# MyProSch1.net
KiCad netlist of a schematic drawn in Altium Designer
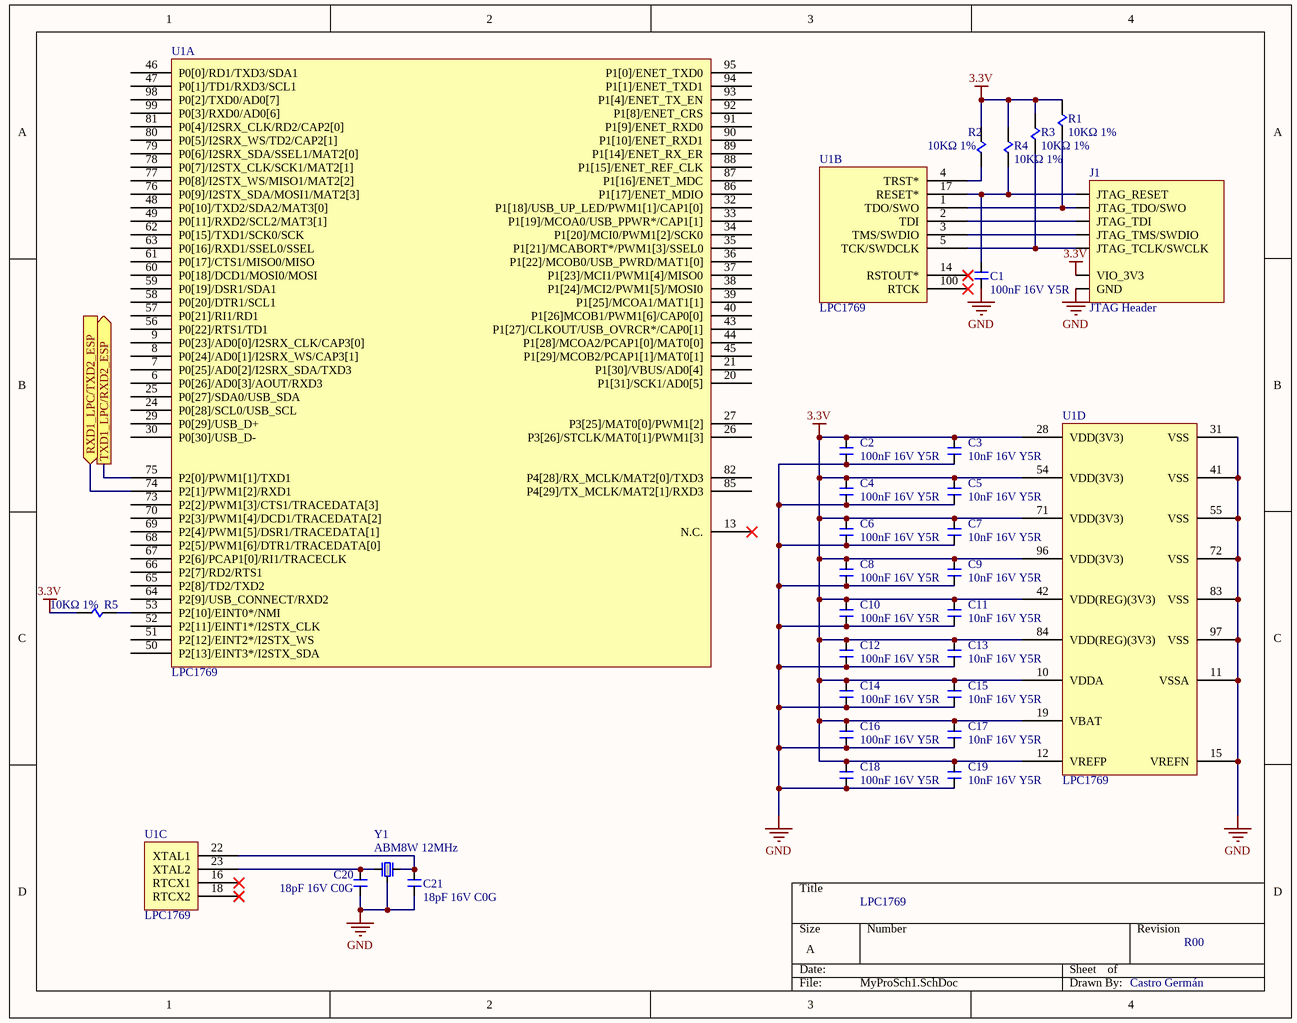
[diagram p0: MyProSch1.SchDoc]

(export (version "E")
  (design (tool "Eeschema 10.0.6"))
  (components
    (comp (ref "C1")
      (value "100nF 16V Y5R")
      (footprint "C_0805")
      (description "Capacitor")
      (libsource (lib "MyPro") (part "Capacitor"))
    )
    (comp (ref "C2")
      (value "100nF 16V Y5R")
      (footprint "C_0805")
      (description "Capacitor")
      (libsource (lib "MyPro") (part "Capacitor"))
    )
    (comp (ref "C3")
      (value "10nF 16V Y5R")
      (footprint "C_0805")
      (description "Capacitor")
      (libsource (lib "MyPro") (part "Capacitor"))
    )
    (comp (ref "C4")
      (value "100nF 16V Y5R")
      (footprint "C_0805")
      (description "Capacitor")
      (libsource (lib "MyPro") (part "Capacitor"))
    )
    (comp (ref "C5")
      (value "10nF 16V Y5R")
      (footprint "C_0805")
      (description "Capacitor")
      (libsource (lib "MyPro") (part "Capacitor"))
    )
    (comp (ref "C6")
      (value "100nF 16V Y5R")
      (footprint "C_0805")
      (description "Capacitor")
      (libsource (lib "MyPro") (part "Capacitor"))
    )
    (comp (ref "C7")
      (value "10nF 16V Y5R")
      (footprint "C_0805")
      (description "Capacitor")
      (libsource (lib "MyPro") (part "Capacitor"))
    )
    (comp (ref "C8")
      (value "100nF 16V Y5R")
      (footprint "C_0805")
      (description "Capacitor")
      (libsource (lib "MyPro") (part "Capacitor"))
    )
    (comp (ref "C9")
      (value "10nF 16V Y5R")
      (footprint "C_0805")
      (description "Capacitor")
      (libsource (lib "MyPro") (part "Capacitor"))
    )
    (comp (ref "C10")
      (value "100nF 16V Y5R")
      (footprint "C_0805")
      (description "Capacitor")
      (libsource (lib "MyPro") (part "Capacitor"))
    )
    (comp (ref "C11")
      (value "10nF 16V Y5R")
      (footprint "C_0805")
      (description "Capacitor")
      (libsource (lib "MyPro") (part "Capacitor"))
    )
    (comp (ref "C12")
      (value "100nF 16V Y5R")
      (footprint "C_0805")
      (description "Capacitor")
      (libsource (lib "MyPro") (part "Capacitor"))
    )
    (comp (ref "C13")
      (value "10nF 16V Y5R")
      (footprint "C_0805")
      (description "Capacitor")
      (libsource (lib "MyPro") (part "Capacitor"))
    )
    (comp (ref "C14")
      (value "100nF 16V Y5R")
      (footprint "C_0805")
      (description "Capacitor")
      (libsource (lib "MyPro") (part "Capacitor"))
    )
    (comp (ref "C15")
      (value "10nF 16V Y5R")
      (footprint "C_0805")
      (description "Capacitor")
      (libsource (lib "MyPro") (part "Capacitor"))
    )
    (comp (ref "C16")
      (value "100nF 16V Y5R")
      (footprint "C_0805")
      (description "Capacitor")
      (libsource (lib "MyPro") (part "Capacitor"))
    )
    (comp (ref "C17")
      (value "10nF 16V Y5R")
      (footprint "C_0805")
      (description "Capacitor")
      (libsource (lib "MyPro") (part "Capacitor"))
    )
    (comp (ref "C18")
      (value "100nF 16V Y5R")
      (footprint "C_0805")
      (description "Capacitor")
      (libsource (lib "MyPro") (part "Capacitor"))
    )
    (comp (ref "C19")
      (value "10nF 16V Y5R")
      (footprint "C_0805")
      (description "Capacitor")
      (libsource (lib "MyPro") (part "Capacitor"))
    )
    (comp (ref "C20")
      (value "18pF 16V C0G")
      (footprint "C_0805")
      (description "Capacitor")
      (libsource (lib "MyPro") (part "Capacitor"))
    )
    (comp (ref "C21")
      (value "18pF 16V C0G")
      (footprint "C_0805")
      (description "Capacitor")
      (libsource (lib "MyPro") (part "Capacitor"))
    )
    (comp (ref "J1") (value "JTAG Header") (libsource (lib "MyPro") (part "JTAG Header")))
    (comp (ref "R1")
      (value "10KΩ 1%")
      (footprint "R_0805")
      (description "Resistor")
      (libsource (lib "MyPro") (part "Resistor"))
    )
    (comp (ref "R2")
      (value "10KΩ 1%")
      (footprint "R_0805")
      (description "Resistor")
      (libsource (lib "MyPro") (part "Resistor"))
    )
    (comp (ref "R3")
      (value "10KΩ 1%")
      (footprint "R_0805")
      (description "Resistor")
      (libsource (lib "MyPro") (part "Resistor"))
    )
    (comp (ref "R4")
      (value "10KΩ 1%")
      (footprint "R_0805")
      (description "Resistor")
      (libsource (lib "MyPro") (part "Resistor"))
    )
    (comp (ref "R5")
      (value "10KΩ 1%")
      (footprint "R_0805")
      (description "Resistor")
      (libsource (lib "MyPro") (part "Resistor"))
    )
    (comp (ref "U1")
      (value "LPC1769")
      (footprint "LQFP100")
      (description "32 bit ARM Cortex M3")
      (libsource (lib "MyPro") (part "LPC1769"))
    )
    (comp (ref "Y1")
      (value "ABM8W 12MHz")
      (footprint "ABM8W")
      (description "Crystal")
      (libsource (lib "MyPro") (part "Crystal"))
    )
  )
  (nets
    (net (code "1") (name "/RXD1_LPC{slash}TXD2_ESP") (class "Default")
      (node (ref "U1") (pin "74") (pinfunction "P2[1]/PWM1[2]/RXD1_74") (pintype "passive"))
    )
    (net (code "2") (name "/TXD1_LPC{slash}RXD2_ESP") (class "Default")
      (node (ref "U1") (pin "75") (pinfunction "P2[0]/PWM1[1]/TXD1_75") (pintype "passive"))
    )
    (net (code "3") (name "3.3V") (class "Default")
      (node (ref "C10") (pin "1") (pinfunction "A1_1") (pintype "passive"))
      (node (ref "C11") (pin "1") (pinfunction "A1_1") (pintype "passive"))
      (node (ref "C12") (pin "1") (pinfunction "A1_1") (pintype "passive"))
      (node (ref "C13") (pin "1") (pinfunction "A1_1") (pintype "passive"))
      (node (ref "C14") (pin "1") (pinfunction "A1_1") (pintype "passive"))
      (node (ref "C15") (pin "1") (pinfunction "A1_1") (pintype "passive"))
      (node (ref "C16") (pin "1") (pinfunction "A1_1") (pintype "passive"))
      (node (ref "C17") (pin "1") (pinfunction "A1_1") (pintype "passive"))
      (node (ref "C18") (pin "1") (pinfunction "A1_1") (pintype "passive"))
      (node (ref "C19") (pin "1") (pinfunction "A1_1") (pintype "passive"))
      (node (ref "C2") (pin "1") (pinfunction "A1_1") (pintype "passive"))
      (node (ref "C3") (pin "1") (pinfunction "A1_1") (pintype "passive"))
      (node (ref "C4") (pin "1") (pinfunction "A1_1") (pintype "passive"))
      (node (ref "C5") (pin "1") (pinfunction "A1_1") (pintype "passive"))
      (node (ref "C6") (pin "1") (pinfunction "A1_1") (pintype "passive"))
      (node (ref "C7") (pin "1") (pinfunction "A1_1") (pintype "passive"))
      (node (ref "C8") (pin "1") (pinfunction "A1_1") (pintype "passive"))
      (node (ref "C9") (pin "1") (pinfunction "A1_1") (pintype "passive"))
      (node (ref "J1") (pin "1") (pinfunction "VIO_3V3_1") (pintype "passive"))
      (node (ref "R1") (pin "2") (pinfunction "P2_2") (pintype "passive"))
      (node (ref "R2") (pin "2") (pinfunction "P2_2") (pintype "passive"))
      (node (ref "R3") (pin "2") (pinfunction "P2_2") (pintype "passive"))
      (node (ref "R4") (pin "2") (pinfunction "P2_2") (pintype "passive"))
      (node (ref "R5") (pin "1") (pinfunction "P1_1") (pintype "passive"))
      (node (ref "U1") (pin "10") (pinfunction "VDDA_10") (pintype "passive"))
      (node (ref "U1") (pin "12") (pinfunction "VREFP_12") (pintype "passive"))
      (node (ref "U1") (pin "19") (pinfunction "VBAT_19") (pintype "passive"))
      (node (ref "U1") (pin "28") (pinfunction "VDD(3V3)_28") (pintype "passive"))
      (node (ref "U1") (pin "42") (pinfunction "VDD(REG)(3V3)_42") (pintype "passive"))
      (node (ref "U1") (pin "54") (pinfunction "VDD(3V3)_54") (pintype "passive"))
      (node (ref "U1") (pin "71") (pinfunction "VDD(3V3)_71") (pintype "passive"))
      (node (ref "U1") (pin "84") (pinfunction "VDD(REG)(3V3)_84") (pintype "passive"))
      (node (ref "U1") (pin "96") (pinfunction "VDD(3V3)_96") (pintype "passive"))
    )
    (net (code "4") (name "GND") (class "Default")
      (node (ref "C1") (pin "2") (pinfunction "A2_2") (pintype "passive"))
      (node (ref "C10") (pin "2") (pinfunction "A2_2") (pintype "passive"))
      (node (ref "C11") (pin "2") (pinfunction "A2_2") (pintype "passive"))
      (node (ref "C12") (pin "2") (pinfunction "A2_2") (pintype "passive"))
      (node (ref "C13") (pin "2") (pinfunction "A2_2") (pintype "passive"))
      (node (ref "C14") (pin "2") (pinfunction "A2_2") (pintype "passive"))
      (node (ref "C15") (pin "2") (pinfunction "A2_2") (pintype "passive"))
      (node (ref "C16") (pin "2") (pinfunction "A2_2") (pintype "passive"))
      (node (ref "C17") (pin "2") (pinfunction "A2_2") (pintype "passive"))
      (node (ref "C18") (pin "2") (pinfunction "A2_2") (pintype "passive"))
      (node (ref "C19") (pin "2") (pinfunction "A2_2") (pintype "passive"))
      (node (ref "C2") (pin "2") (pinfunction "A2_2") (pintype "passive"))
      (node (ref "C20") (pin "2") (pinfunction "A2_2") (pintype "passive"))
      (node (ref "C21") (pin "2") (pinfunction "A2_2") (pintype "passive"))
      (node (ref "C3") (pin "2") (pinfunction "A2_2") (pintype "passive"))
      (node (ref "C4") (pin "2") (pinfunction "A2_2") (pintype "passive"))
      (node (ref "C5") (pin "2") (pinfunction "A2_2") (pintype "passive"))
      (node (ref "C6") (pin "2") (pinfunction "A2_2") (pintype "passive"))
      (node (ref "C7") (pin "2") (pinfunction "A2_2") (pintype "passive"))
      (node (ref "C8") (pin "2") (pinfunction "A2_2") (pintype "passive"))
      (node (ref "C9") (pin "2") (pinfunction "A2_2") (pintype "passive"))
      (node (ref "J1") (pin "8") (pinfunction "GND_8") (pintype "passive"))
      (node (ref "U1") (pin "11") (pinfunction "VSSA_11") (pintype "passive"))
      (node (ref "U1") (pin "15") (pinfunction "VREFN_15") (pintype "passive"))
      (node (ref "U1") (pin "31") (pinfunction "VSS_31") (pintype "passive"))
      (node (ref "U1") (pin "41") (pinfunction "VSS_41") (pintype "passive"))
      (node (ref "U1") (pin "55") (pinfunction "VSS_55") (pintype "passive"))
      (node (ref "U1") (pin "72") (pinfunction "VSS_72") (pintype "passive"))
      (node (ref "U1") (pin "83") (pinfunction "VSS_83") (pintype "passive"))
      (node (ref "U1") (pin "97") (pinfunction "VSS_97") (pintype "passive"))
      (node (ref "Y1") (pin "3") (pinfunction "P3_3") (pintype "passive"))
    )
    (net (code "5") (name "Net-(C1-A1)") (class "Default")
      (node (ref "C1") (pin "1") (pinfunction "A1_1") (pintype "passive"))
      (node (ref "J1") (pin "6") (pinfunction "JTAG_RESET_6") (pintype "passive"))
      (node (ref "R4") (pin "1") (pinfunction "P1_1") (pintype "passive"))
      (node (ref "U1") (pin "17") (pinfunction "RESET*_17") (pintype "passive"))
    )
    (net (code "6") (name "Net-(C20-A1)") (class "Default")
      (node (ref "C20") (pin "1") (pinfunction "A1_1") (pintype "passive"))
      (node (ref "U1") (pin "23") (pinfunction "XTAL2_23") (pintype "passive"))
      (node (ref "Y1") (pin "1") (pinfunction "P1_1") (pintype "passive"))
    )
    (net (code "7") (name "Net-(C21-A1)") (class "Default")
      (node (ref "C21") (pin "1") (pinfunction "A1_1") (pintype "passive"))
      (node (ref "U1") (pin "22") (pinfunction "XTAL1_22") (pintype "passive"))
      (node (ref "Y1") (pin "2") (pinfunction "P2_2") (pintype "passive"))
    )
    (net (code "8") (name "Net-(J1-JTAG_TCLK{slash}SWCLK)") (class "Default")
      (node (ref "J1") (pin "3") (pinfunction "JTAG_TCLK/SWCLK_3") (pintype "passive"))
      (node (ref "R3") (pin "1") (pinfunction "P1_1") (pintype "passive"))
      (node (ref "U1") (pin "5") (pinfunction "TCK/SWDCLK_5") (pintype "passive"))
    )
    (net (code "9") (name "Net-(J1-JTAG_TDI)") (class "Default")
      (node (ref "J1") (pin "5") (pinfunction "JTAG_TDI_5") (pintype "passive"))
      (node (ref "U1") (pin "2") (pinfunction "TDI_2") (pintype "passive"))
    )
    (net (code "10") (name "Net-(J1-JTAG_TDO{slash}SWO)") (class "Default")
      (node (ref "J1") (pin "4") (pinfunction "JTAG_TDO/SWO_4") (pintype "passive"))
      (node (ref "R1") (pin "1") (pinfunction "P1_1") (pintype "passive"))
      (node (ref "U1") (pin "1") (pinfunction "TDO/SWO_1") (pintype "passive"))
    )
    (net (code "11") (name "Net-(J1-JTAG_TMS{slash}SWDIO)") (class "Default")
      (node (ref "J1") (pin "2") (pinfunction "JTAG_TMS/SWDIO_2") (pintype "passive"))
      (node (ref "U1") (pin "3") (pinfunction "TMS/SWDIO_3") (pintype "passive"))
    )
    (net (code "12") (name "Net-(R2-P1)") (class "Default")
      (node (ref "R2") (pin "1") (pinfunction "P1_1") (pintype "passive"))
      (node (ref "U1") (pin "4") (pinfunction "TRST*_4") (pintype "passive"))
    )
    (net (code "13") (name "Net-(R5-P2)") (class "Default")
      (node (ref "R5") (pin "2") (pinfunction "P2_2") (pintype "passive"))
      (node (ref "U1") (pin "53") (pinfunction "P2[10]/EINT0*/NMI_53") (pintype "passive"))
    )
    (net (code "14") (name "unconnected-(U1A-N.C.-Pad13)") (class "Default")
      (node (ref "U1") (pin "13") (pinfunction "N.C._13") (pintype "passive+no_connect"))
    )
    (net (code "15") (name "unconnected-(U1A-P0[0]{slash}RD1{slash}TXD3{slash}SDA1-Pad46)") (class "Default")
      (node (ref "U1") (pin "46") (pinfunction "P0[0]/RD1/TXD3/SDA1_46") (pintype "passive"))
    )
    (net (code "16") (name "unconnected-(U1A-P0[1]{slash}TD1{slash}RXD3{slash}SCL1-Pad47)") (class "Default")
      (node (ref "U1") (pin "47") (pinfunction "P0[1]/TD1/RXD3/SCL1_47") (pintype "passive"))
    )
    (net (code "17") (name "unconnected-(U1A-P0[2]{slash}TXD0{slash}AD0[7]-Pad98)") (class "Default")
      (node (ref "U1") (pin "98") (pinfunction "P0[2]/TXD0/AD0[7]_98") (pintype "passive"))
    )
    (net (code "18") (name "unconnected-(U1A-P0[3]{slash}RXD0{slash}AD0[6]-Pad99)") (class "Default")
      (node (ref "U1") (pin "99") (pinfunction "P0[3]/RXD0/AD0[6]_99") (pintype "passive"))
    )
    (net (code "19") (name "unconnected-(U1A-P0[4]{slash}I2SRX_CLK{slash}RD2{slash}CAP2[0]-Pad81)") (class "Default")
      (node (ref "U1") (pin "81") (pinfunction "P0[4]/I2SRX_CLK/RD2/CAP2[0]_81") (pintype "passive"))
    )
    (net (code "20") (name "unconnected-(U1A-P0[5]{slash}I2SRX_WS{slash}TD2{slash}CAP2[1]-Pad80)") (class "Default")
      (node (ref "U1") (pin "80") (pinfunction "P0[5]/I2SRX_WS/TD2/CAP2[1]_80") (pintype "passive"))
    )
    (net (code "21") (name "unconnected-(U1A-P0[6]{slash}I2SRX_SDA{slash}SSEL1{slash}MAT2[0]-Pad79)") (class "Default")
      (node (ref "U1") (pin "79") (pinfunction "P0[6]/I2SRX_SDA/SSEL1/MAT2[0]_79") (pintype "passive"))
    )
    (net (code "22") (name "unconnected-(U1A-P0[7]{slash}I2STX_CLK{slash}SCK1{slash}MAT2[1]-Pad78)") (class "Default")
      (node (ref "U1") (pin "78") (pinfunction "P0[7]/I2STX_CLK/SCK1/MAT2[1]_78") (pintype "passive"))
    )
    (net (code "23") (name "unconnected-(U1A-P0[8]{slash}I2STX_WS{slash}MISO1{slash}MAT2[2]-Pad77)") (class "Default")
      (node (ref "U1") (pin "77") (pinfunction "P0[8]/I2STX_WS/MISO1/MAT2[2]_77") (pintype "passive"))
    )
    (net (code "24") (name "unconnected-(U1A-P0[9]{slash}I2STX_SDA{slash}MOSI1{slash}MAT2[3]-Pad76)") (class "Default")
      (node (ref "U1") (pin "76") (pinfunction "P0[9]/I2STX_SDA/MOSI1/MAT2[3]_76") (pintype "passive"))
    )
    (net (code "25") (name "unconnected-(U1A-P0[10]{slash}TXD2{slash}SDA2{slash}MAT3[0]-Pad48)") (class "Default")
      (node (ref "U1") (pin "48") (pinfunction "P0[10]/TXD2/SDA2/MAT3[0]_48") (pintype "passive"))
    )
    (net (code "26") (name "unconnected-(U1A-P0[11]{slash}RXD2{slash}SCL2{slash}MAT3[1]-Pad49)") (class "Default")
      (node (ref "U1") (pin "49") (pinfunction "P0[11]/RXD2/SCL2/MAT3[1]_49") (pintype "passive"))
    )
    (net (code "27") (name "unconnected-(U1A-P0[15]{slash}TXD1{slash}SCK0{slash}SCK-Pad62)") (class "Default")
      (node (ref "U1") (pin "62") (pinfunction "P0[15]/TXD1/SCK0/SCK_62") (pintype "passive"))
    )
    (net (code "28") (name "unconnected-(U1A-P0[16]{slash}RXD1{slash}SSEL0{slash}SSEL-Pad63)") (class "Default")
      (node (ref "U1") (pin "63") (pinfunction "P0[16]/RXD1/SSEL0/SSEL_63") (pintype "passive"))
    )
    (net (code "29") (name "unconnected-(U1A-P0[17]{slash}CTS1{slash}MISO0{slash}MISO-Pad61)") (class "Default")
      (node (ref "U1") (pin "61") (pinfunction "P0[17]/CTS1/MISO0/MISO_61") (pintype "passive"))
    )
    (net (code "30") (name "unconnected-(U1A-P0[18]{slash}DCD1{slash}MOSI0{slash}MOSI-Pad60)") (class "Default")
      (node (ref "U1") (pin "60") (pinfunction "P0[18]/DCD1/MOSI0/MOSI_60") (pintype "passive"))
    )
    (net (code "31") (name "unconnected-(U1A-P0[19]{slash}DSR1{slash}SDA1-Pad59)") (class "Default")
      (node (ref "U1") (pin "59") (pinfunction "P0[19]/DSR1/SDA1_59") (pintype "passive"))
    )
    (net (code "32") (name "unconnected-(U1A-P0[20]{slash}DTR1{slash}SCL1-Pad58)") (class "Default")
      (node (ref "U1") (pin "58") (pinfunction "P0[20]/DTR1/SCL1_58") (pintype "passive"))
    )
    (net (code "33") (name "unconnected-(U1A-P0[21]{slash}RI1{slash}RD1-Pad57)") (class "Default")
      (node (ref "U1") (pin "57") (pinfunction "P0[21]/RI1/RD1_57") (pintype "passive"))
    )
    (net (code "34") (name "unconnected-(U1A-P0[22]{slash}RTS1{slash}TD1-Pad56)") (class "Default")
      (node (ref "U1") (pin "56") (pinfunction "P0[22]/RTS1/TD1_56") (pintype "passive"))
    )
    (net (code "35") (name "unconnected-(U1A-P0[23]{slash}AD0[0]{slash}I2SRX_CLK{slash}CAP3[0]-Pad9)") (class "Default")
      (node (ref "U1") (pin "9") (pinfunction "P0[23]/AD0[0]/I2SRX_CLK/CAP3[0]_9") (pintype "passive"))
    )
    (net (code "36") (name "unconnected-(U1A-P0[24]{slash}AD0[1]{slash}I2SRX_WS{slash}CAP3[1]-Pad8)") (class "Default")
      (node (ref "U1") (pin "8") (pinfunction "P0[24]/AD0[1]/I2SRX_WS/CAP3[1]_8") (pintype "passive"))
    )
    (net (code "37") (name "unconnected-(U1A-P0[25]{slash}AD0[2]{slash}I2SRX_SDA{slash}TXD3-Pad7)") (class "Default")
      (node (ref "U1") (pin "7") (pinfunction "P0[25]/AD0[2]/I2SRX_SDA/TXD3_7") (pintype "passive"))
    )
    (net (code "38") (name "unconnected-(U1A-P0[26]{slash}AD0[3]{slash}AOUT{slash}RXD3-Pad6)") (class "Default")
      (node (ref "U1") (pin "6") (pinfunction "P0[26]/AD0[3]/AOUT/RXD3_6") (pintype "passive"))
    )
    (net (code "39") (name "unconnected-(U1A-P0[27]{slash}SDA0{slash}USB_SDA-Pad25)") (class "Default")
      (node (ref "U1") (pin "25") (pinfunction "P0[27]/SDA0/USB_SDA_25") (pintype "passive"))
    )
    (net (code "40") (name "unconnected-(U1A-P0[28]{slash}SCL0{slash}USB_SCL-Pad24)") (class "Default")
      (node (ref "U1") (pin "24") (pinfunction "P0[28]/SCL0/USB_SCL_24") (pintype "passive"))
    )
    (net (code "41") (name "unconnected-(U1A-P0[29]{slash}USB_D+-Pad29)") (class "Default")
      (node (ref "U1") (pin "29") (pinfunction "P0[29]/USB_D+_29") (pintype "passive"))
    )
    (net (code "42") (name "unconnected-(U1A-P0[30]{slash}USB_D--Pad30)") (class "Default")
      (node (ref "U1") (pin "30") (pinfunction "P0[30]/USB_D-_30") (pintype "passive"))
    )
    (net (code "43") (name "unconnected-(U1A-P1[0]{slash}ENET_TXD0-Pad95)") (class "Default")
      (node (ref "U1") (pin "95") (pinfunction "P1[0]/ENET_TXD0_95") (pintype "passive"))
    )
    (net (code "44") (name "unconnected-(U1A-P1[1]{slash}ENET_TXD1-Pad94)") (class "Default")
      (node (ref "U1") (pin "94") (pinfunction "P1[1]/ENET_TXD1_94") (pintype "passive"))
    )
    (net (code "45") (name "unconnected-(U1A-P1[4]{slash}ENET_TX_EN-Pad93)") (class "Default")
      (node (ref "U1") (pin "93") (pinfunction "P1[4]/ENET_TX_EN_93") (pintype "passive"))
    )
    (net (code "46") (name "unconnected-(U1A-P1[8]{slash}ENET_CRS-Pad92)") (class "Default")
      (node (ref "U1") (pin "92") (pinfunction "P1[8]/ENET_CRS_92") (pintype "passive"))
    )
    (net (code "47") (name "unconnected-(U1A-P1[9]{slash}ENET_RXD0-Pad91)") (class "Default")
      (node (ref "U1") (pin "91") (pinfunction "P1[9]/ENET_RXD0_91") (pintype "passive"))
    )
    (net (code "48") (name "unconnected-(U1A-P1[10]{slash}ENET_RXD1-Pad90)") (class "Default")
      (node (ref "U1") (pin "90") (pinfunction "P1[10]/ENET_RXD1_90") (pintype "passive"))
    )
    (net (code "49") (name "unconnected-(U1A-P1[14]{slash}ENET_RX_ER-Pad89)") (class "Default")
      (node (ref "U1") (pin "89") (pinfunction "P1[14]/ENET_RX_ER_89") (pintype "passive"))
    )
    (net (code "50") (name "unconnected-(U1A-P1[15]{slash}ENET_REF_CLK-Pad88)") (class "Default")
      (node (ref "U1") (pin "88") (pinfunction "P1[15]/ENET_REF_CLK_88") (pintype "passive"))
    )
    (net (code "51") (name "unconnected-(U1A-P1[16]{slash}ENET_MDC-Pad87)") (class "Default")
      (node (ref "U1") (pin "87") (pinfunction "P1[16]/ENET_MDC_87") (pintype "passive"))
    )
    (net (code "52") (name "unconnected-(U1A-P1[17]{slash}ENET_MDIO-Pad86)") (class "Default")
      (node (ref "U1") (pin "86") (pinfunction "P1[17]/ENET_MDIO_86") (pintype "passive"))
    )
    (net (code "53") (name "unconnected-(U1A-P1[18]{slash}USB_UP_LED{slash}PWM1[1]{slash}CAP1[0]-Pad32)") (class "Default")
      (node (ref "U1") (pin "32") (pinfunction "P1[18]/USB_UP_LED/PWM1[1]/CAP1[0]_32") (pintype "passive"))
    )
    (net (code "54") (name "unconnected-(U1A-P1[19]{slash}MCOA0{slash}USB_PPWR*{slash}CAP1[1]-Pad33)") (class "Default")
      (node (ref "U1") (pin "33") (pinfunction "P1[19]/MCOA0/USB_PPWR*/CAP1[1]_33") (pintype "passive"))
    )
    (net (code "55") (name "unconnected-(U1A-P1[20]{slash}MCI0{slash}PWM1[2]{slash}SCK0-Pad34)") (class "Default")
      (node (ref "U1") (pin "34") (pinfunction "P1[20]/MCI0/PWM1[2]/SCK0_34") (pintype "passive"))
    )
    (net (code "56") (name "unconnected-(U1A-P1[21]{slash}MCABORT*{slash}PWM1[3]{slash}SSEL0-Pad35)") (class "Default")
      (node (ref "U1") (pin "35") (pinfunction "P1[21]/MCABORT*/PWM1[3]/SSEL0_35") (pintype "passive"))
    )
    (net (code "57") (name "unconnected-(U1A-P1[22]{slash}MCOB0{slash}USB_PWRD{slash}MAT1[0]-Pad36)") (class "Default")
      (node (ref "U1") (pin "36") (pinfunction "P1[22]/MCOB0/USB_PWRD/MAT1[0]_36") (pintype "passive"))
    )
    (net (code "58") (name "unconnected-(U1A-P1[23]{slash}MCI1{slash}PWM1[4]{slash}MISO0-Pad37)") (class "Default")
      (node (ref "U1") (pin "37") (pinfunction "P1[23]/MCI1/PWM1[4]/MISO0_37") (pintype "passive"))
    )
    (net (code "59") (name "unconnected-(U1A-P1[24]{slash}MCI2{slash}PWM1[5]{slash}MOSI0-Pad38)") (class "Default")
      (node (ref "U1") (pin "38") (pinfunction "P1[24]/MCI2/PWM1[5]/MOSI0_38") (pintype "passive"))
    )
    (net (code "60") (name "unconnected-(U1A-P1[25]{slash}MCOA1{slash}MAT1[1]-Pad39)") (class "Default")
      (node (ref "U1") (pin "39") (pinfunction "P1[25]/MCOA1/MAT1[1]_39") (pintype "passive"))
    )
    (net (code "61") (name "unconnected-(U1A-P1[26]MCOB1{slash}PWM1[6]{slash}CAP0[0]-Pad40)") (class "Default")
      (node (ref "U1") (pin "40") (pinfunction "P1[26]MCOB1/PWM1[6]/CAP0[0]_40") (pintype "passive"))
    )
    (net (code "62") (name "unconnected-(U1A-P1[27]{slash}CLKOUT{slash}USB_OVRCR*{slash}CAP0[1]-Pad43)") (class "Default")
      (node (ref "U1") (pin "43") (pinfunction "P1[27]/CLKOUT/USB_OVRCR*/CAP0[1]_43") (pintype "passive"))
    )
    (net (code "63") (name "unconnected-(U1A-P1[28]{slash}MCOA2{slash}PCAP1[0]{slash}MAT0[0]-Pad44)") (class "Default")
      (node (ref "U1") (pin "44") (pinfunction "P1[28]/MCOA2/PCAP1[0]/MAT0[0]_44") (pintype "passive"))
    )
    (net (code "64") (name "unconnected-(U1A-P1[29]{slash}MCOB2{slash}PCAP1[1]{slash}MAT0[1]-Pad45)") (class "Default")
      (node (ref "U1") (pin "45") (pinfunction "P1[29]/MCOB2/PCAP1[1]/MAT0[1]_45") (pintype "passive"))
    )
    (net (code "65") (name "unconnected-(U1A-P1[30]{slash}VBUS{slash}AD0[4]-Pad21)") (class "Default")
      (node (ref "U1") (pin "21") (pinfunction "P1[30]/VBUS/AD0[4]_21") (pintype "passive"))
    )
    (net (code "66") (name "unconnected-(U1A-P1[31]{slash}SCK1{slash}AD0[5]-Pad20)") (class "Default")
      (node (ref "U1") (pin "20") (pinfunction "P1[31]/SCK1/AD0[5]_20") (pintype "passive"))
    )
    (net (code "67") (name "unconnected-(U1A-P2[2]{slash}PWM1[3]{slash}CTS1{slash}TRACEDATA[3]-Pad73)") (class "Default")
      (node (ref "U1") (pin "73") (pinfunction "P2[2]/PWM1[3]/CTS1/TRACEDATA[3]_73") (pintype "passive"))
    )
    (net (code "68") (name "unconnected-(U1A-P2[3]{slash}PWM1[4]{slash}DCD1{slash}TRACEDATA[2]-Pad70)") (class "Default")
      (node (ref "U1") (pin "70") (pinfunction "P2[3]/PWM1[4]/DCD1/TRACEDATA[2]_70") (pintype "passive"))
    )
    (net (code "69") (name "unconnected-(U1A-P2[4]{slash}PWM1[5]{slash}DSR1{slash}TRACEDATA[1]-Pad69)") (class "Default")
      (node (ref "U1") (pin "69") (pinfunction "P2[4]/PWM1[5]/DSR1/TRACEDATA[1]_69") (pintype "passive"))
    )
    (net (code "70") (name "unconnected-(U1A-P2[5]{slash}PWM1[6]{slash}DTR1{slash}TRACEDATA[0]-Pad68)") (class "Default")
      (node (ref "U1") (pin "68") (pinfunction "P2[5]/PWM1[6]/DTR1/TRACEDATA[0]_68") (pintype "passive"))
    )
    (net (code "71") (name "unconnected-(U1A-P2[6]{slash}PCAP1[0]{slash}RI1{slash}TRACECLK-Pad67)") (class "Default")
      (node (ref "U1") (pin "67") (pinfunction "P2[6]/PCAP1[0]/RI1/TRACECLK_67") (pintype "passive"))
    )
    (net (code "72") (name "unconnected-(U1A-P2[7]{slash}RD2{slash}RTS1-Pad66)") (class "Default")
      (node (ref "U1") (pin "66") (pinfunction "P2[7]/RD2/RTS1_66") (pintype "passive"))
    )
    (net (code "73") (name "unconnected-(U1A-P2[8]{slash}TD2{slash}TXD2-Pad65)") (class "Default")
      (node (ref "U1") (pin "65") (pinfunction "P2[8]/TD2/TXD2_65") (pintype "passive"))
    )
    (net (code "74") (name "unconnected-(U1A-P2[9]{slash}USB_CONNECT{slash}RXD2-Pad64)") (class "Default")
      (node (ref "U1") (pin "64") (pinfunction "P2[9]/USB_CONNECT/RXD2_64") (pintype "passive"))
    )
    (net (code "75") (name "unconnected-(U1A-P2[11]{slash}EINT1*{slash}I2STX_CLK-Pad52)") (class "Default")
      (node (ref "U1") (pin "52") (pinfunction "P2[11]/EINT1*/I2STX_CLK_52") (pintype "passive"))
    )
    (net (code "76") (name "unconnected-(U1A-P2[12]{slash}EINT2*{slash}I2STX_WS-Pad51)") (class "Default")
      (node (ref "U1") (pin "51") (pinfunction "P2[12]/EINT2*/I2STX_WS_51") (pintype "passive"))
    )
    (net (code "77") (name "unconnected-(U1A-P2[13]{slash}EINT3*{slash}I2STX_SDA-Pad50)") (class "Default")
      (node (ref "U1") (pin "50") (pinfunction "P2[13]/EINT3*/I2STX_SDA_50") (pintype "passive"))
    )
    (net (code "78") (name "unconnected-(U1A-P3[25]{slash}MAT0[0]{slash}PWM1[2]-Pad27)") (class "Default")
      (node (ref "U1") (pin "27") (pinfunction "P3[25]/MAT0[0]/PWM1[2]_27") (pintype "passive"))
    )
    (net (code "79") (name "unconnected-(U1A-P3[26]{slash}STCLK{slash}MAT0[1]{slash}PWM1[3]-Pad26)") (class "Default")
      (node (ref "U1") (pin "26") (pinfunction "P3[26]/STCLK/MAT0[1]/PWM1[3]_26") (pintype "passive"))
    )
    (net (code "80") (name "unconnected-(U1A-P4[28]{slash}RX_MCLK{slash}MAT2[0]{slash}TXD3-Pad82)") (class "Default")
      (node (ref "U1") (pin "82") (pinfunction "P4[28]/RX_MCLK/MAT2[0]/TXD3_82") (pintype "passive"))
    )
    (net (code "81") (name "unconnected-(U1A-P4[29]{slash}TX_MCLK{slash}MAT2[1]{slash}RXD3-Pad85)") (class "Default")
      (node (ref "U1") (pin "85") (pinfunction "P4[29]/TX_MCLK/MAT2[1]/RXD3_85") (pintype "passive"))
    )
    (net (code "82") (name "unconnected-(U1B-RSTOUT*-Pad14)") (class "Default")
      (node (ref "U1") (pin "14") (pinfunction "RSTOUT*_14") (pintype "passive+no_connect"))
    )
    (net (code "83") (name "unconnected-(U1B-RTCK-Pad100)") (class "Default")
      (node (ref "U1") (pin "100") (pinfunction "RTCK_100") (pintype "passive+no_connect"))
    )
    (net (code "84") (name "unconnected-(U1C-RTCX1-Pad16)") (class "Default")
      (node (ref "U1") (pin "16") (pinfunction "RTCX1_16") (pintype "passive+no_connect"))
    )
    (net (code "85") (name "unconnected-(U1C-RTCX2-Pad18)") (class "Default")
      (node (ref "U1") (pin "18") (pinfunction "RTCX2_18") (pintype "passive+no_connect"))
    )
  )
)
